# ina219.net
KiCad netlist of a schematic drawn in EAGLE
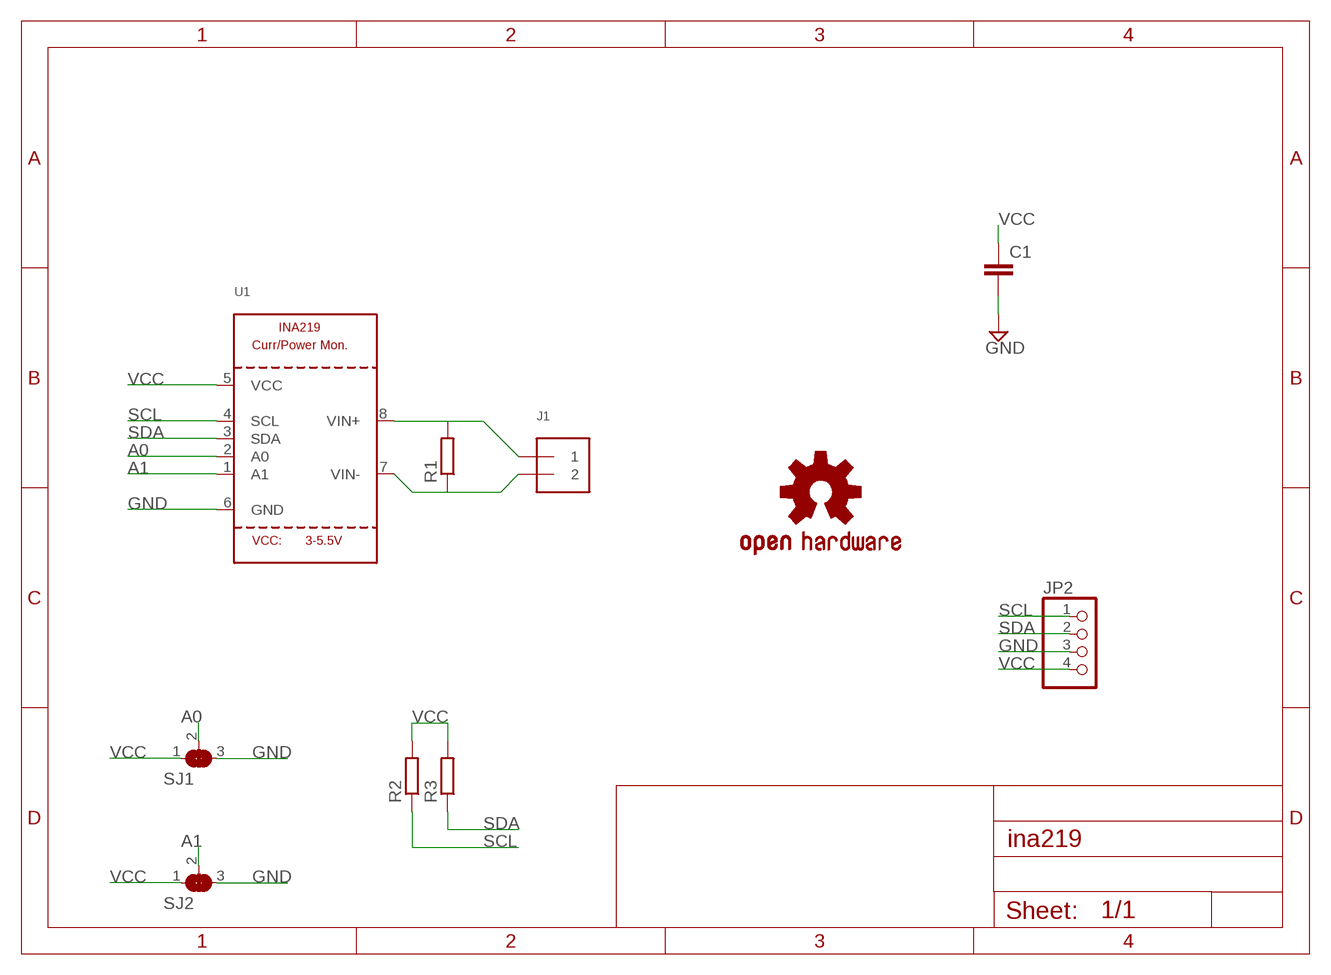
[diagram p0: schematic, sheet 1]

(export (version "E")
  (design (tool "Eeschema 10.0.6"))
  (components
    (comp (ref "C1")
      (value "C-EUC0805")
      (footprint "eagle-import:C0805")
      (libsource (lib "eagle-import") (part "C-EUC0805"))
    )
    (comp (ref "J1")
      (value "TERMBLOCK_1X2")
      (footprint "eagle-import:TERMBLOCK_1X2-3.5MM")
      (libsource (lib "eagle-import") (part "TERMBLOCK_1X2"))
    )
    (comp (ref "JP2")
      (value "PINHD-1X4")
      (footprint "eagle-import:1X04")
      (libsource (lib "eagle-import") (part "PINHD-1X4"))
    )
    (comp (ref "LOGO1")
      (value "OSHW-LOGOS")
      (footprint "eagle-import:OSHW-LOGO-S")
      (libsource (lib "eagle-import") (part "OSHW-LOGOS"))
    )
    (comp (ref "R1")
      (value "R-EU_R1206")
      (footprint "eagle-import:R1206")
      (libsource (lib "eagle-import") (part "R-EU_R1206"))
    )
    (comp (ref "R2")
      (value "R-EU_R0805")
      (footprint "eagle-import:R0805")
      (libsource (lib "eagle-import") (part "R-EU_R0805"))
    )
    (comp (ref "R3")
      (value "R-EU_R0805")
      (footprint "eagle-import:R0805")
      (libsource (lib "eagle-import") (part "R-EU_R0805"))
    )
    (comp (ref "SJ1")
      (value "SOLDERJUMPER_2WAY0603")
      (footprint "eagle-import:SOLDERJUMPER_2WAY_OPEN_0603")
      (libsource (lib "eagle-import") (part "SOLDERJUMPER_2WAY0603"))
    )
    (comp (ref "SJ2")
      (value "SOLDERJUMPER_2WAY0603")
      (footprint "eagle-import:SOLDERJUMPER_2WAY_OPEN_0603")
      (libsource (lib "eagle-import") (part "SOLDERJUMPER_2WAY0603"))
    )
    (comp (ref "U1")
      (value "INA219SOIC8")
      (footprint "eagle-import:SOIC8_150MIL")
      (libsource (lib "eagle-import") (part "INA219SOIC8"))
    )
  )
  (nets
    (net (code "1") (name "/A0") (class "Default")
      (node (ref "SJ1") (pin "2") (pinfunction "2_2") (pintype "passive"))
      (node (ref "U1") (pin "2") (pinfunction "A0_2") (pintype "bidirectional"))
    )
    (net (code "2") (name "/A1") (class "Default")
      (node (ref "SJ2") (pin "2") (pinfunction "2_2") (pintype "passive"))
      (node (ref "U1") (pin "1") (pinfunction "A1_1") (pintype "bidirectional"))
    )
    (net (code "3") (name "/SCL") (class "Default")
      (node (ref "JP2") (pin "1") (pinfunction "1_1") (pintype "passive"))
      (node (ref "R2") (pin "1") (pinfunction "1_1") (pintype "passive"))
      (node (ref "U1") (pin "4") (pinfunction "SCL_4") (pintype "bidirectional"))
    )
    (net (code "4") (name "/SDA") (class "Default")
      (node (ref "JP2") (pin "2") (pinfunction "2_2") (pintype "passive"))
      (node (ref "R3") (pin "1") (pinfunction "1_1") (pintype "passive"))
      (node (ref "U1") (pin "3") (pinfunction "SDA_3") (pintype "bidirectional"))
    )
    (net (code "5") (name "/VCC") (class "Default")
      (node (ref "C1") (pin "1") (pinfunction "1_1") (pintype "passive"))
      (node (ref "JP2") (pin "4") (pinfunction "4_4") (pintype "passive"))
      (node (ref "R2") (pin "2") (pinfunction "2_2") (pintype "passive"))
      (node (ref "R3") (pin "2") (pinfunction "2_2") (pintype "passive"))
      (node (ref "SJ1") (pin "1") (pinfunction "1_1") (pintype "passive"))
      (node (ref "SJ2") (pin "1") (pinfunction "1_1") (pintype "passive"))
      (node (ref "U1") (pin "5") (pinfunction "VCC_5") (pintype "bidirectional"))
    )
    (net (code "6") (name "GND") (class "Default")
      (node (ref "C1") (pin "2") (pinfunction "2_2") (pintype "passive"))
      (node (ref "JP2") (pin "3") (pinfunction "3_3") (pintype "passive"))
      (node (ref "SJ1") (pin "3") (pinfunction "3_3") (pintype "passive"))
      (node (ref "SJ2") (pin "3") (pinfunction "3_3") (pintype "passive"))
      (node (ref "U1") (pin "6") (pinfunction "GND_6") (pintype "bidirectional"))
    )
    (net (code "7") (name "Net-(U1-VIN+)") (class "Default")
      (node (ref "J1") (pin "1") (pinfunction "1_1") (pintype "passive"))
      (node (ref "R1") (pin "2") (pinfunction "2_2") (pintype "passive"))
      (node (ref "U1") (pin "8") (pinfunction "VIN+_8") (pintype "bidirectional"))
    )
    (net (code "8") (name "Net-(U1-VIN-)") (class "Default")
      (node (ref "J1") (pin "2") (pinfunction "2_2") (pintype "passive"))
      (node (ref "R1") (pin "1") (pinfunction "1_1") (pintype "passive"))
      (node (ref "U1") (pin "7") (pinfunction "VIN-_7") (pintype "bidirectional"))
    )
  )
)
